# arca-2_0-box.net
KiCad netlist of a schematic drawn in EAGLE
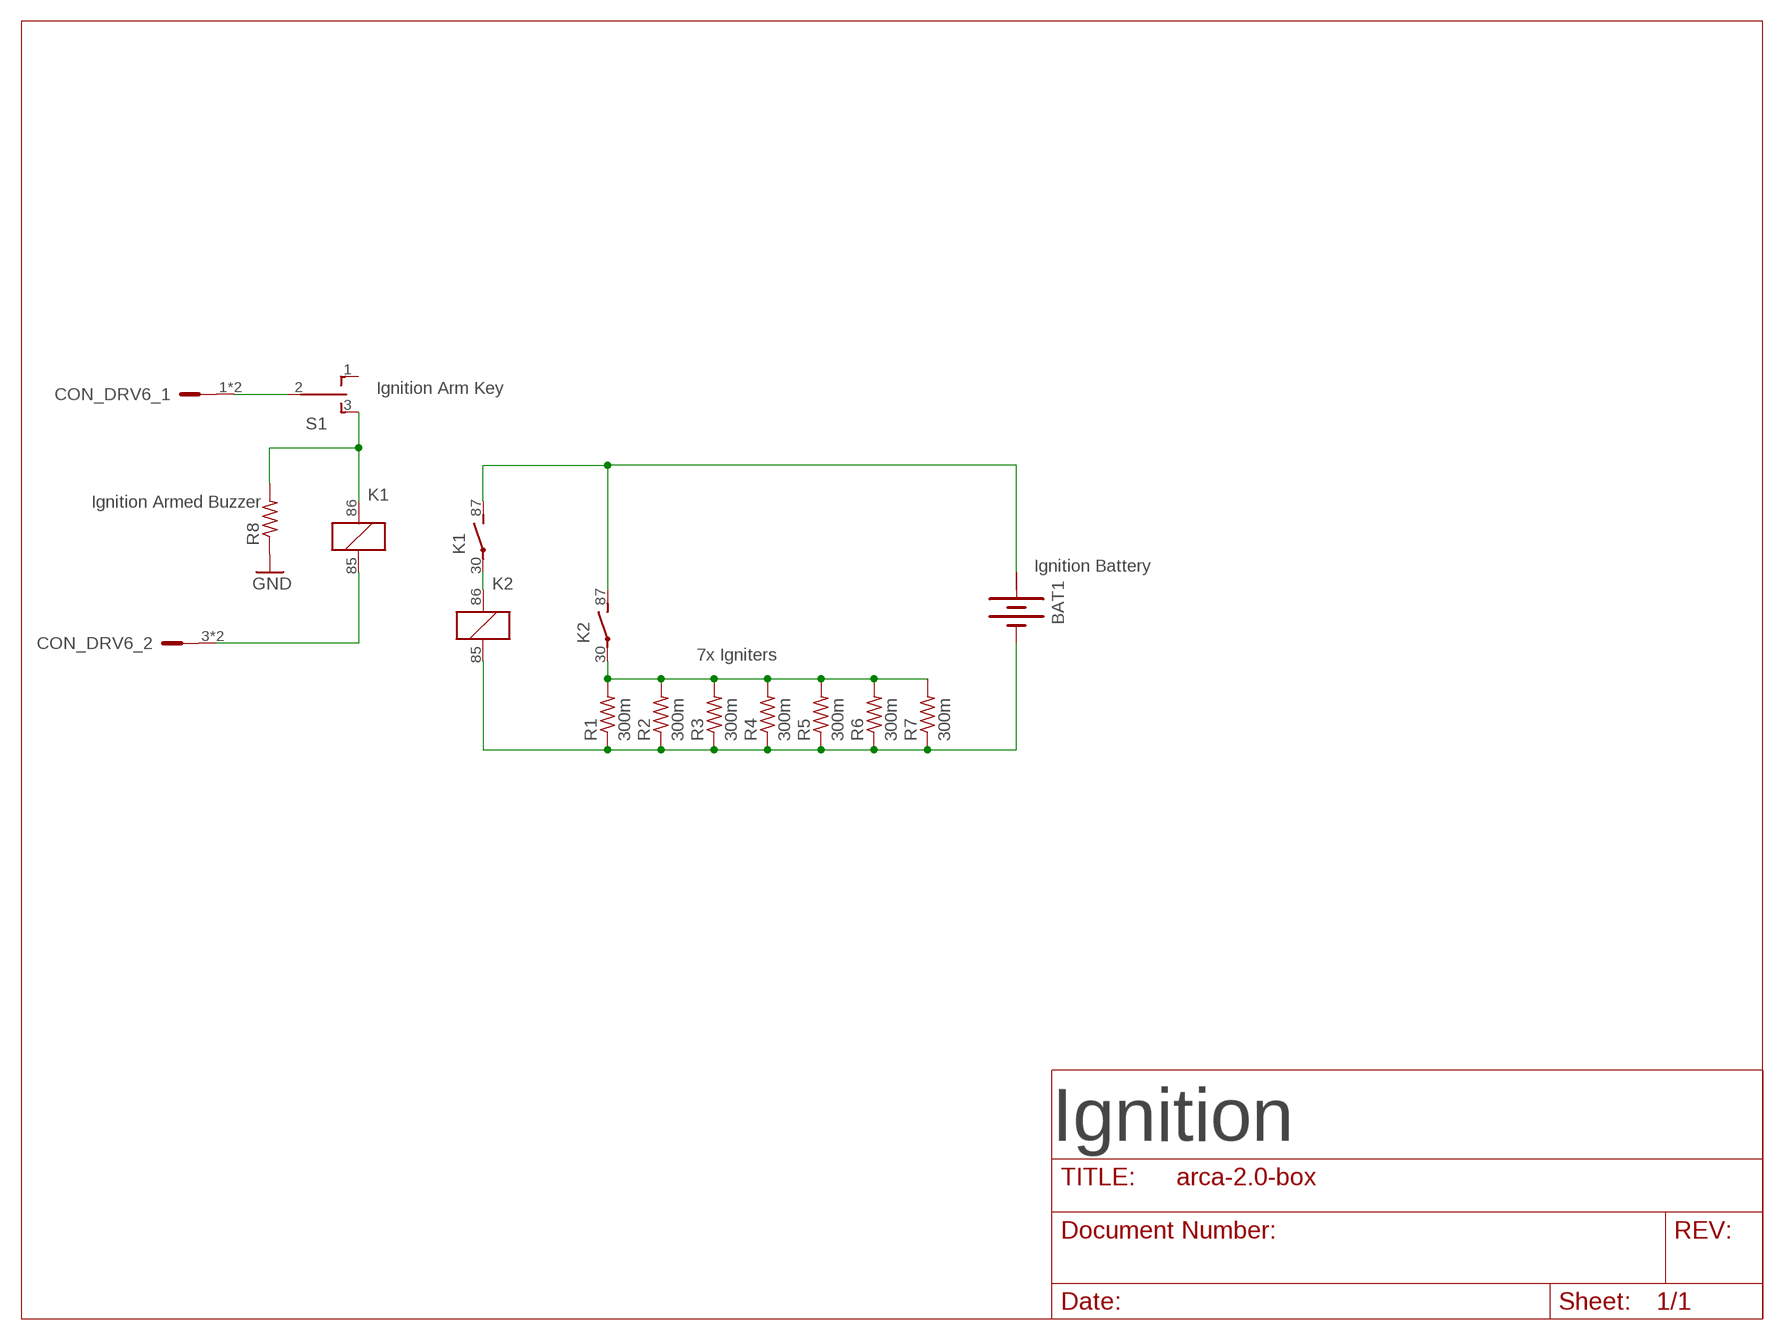
[diagram p0: schematic, sheet 1]

(export (version "E")
  (design (tool "Eeschema 10.0.6"))
  (components
    (comp (ref "BAT1")
      (value "BATTERY")
      (footprint "eagle-import:BATTERY")
      (libsource (lib "eagle-import") (part "BATTERY"))
    )
    (comp (ref "CON_DRV6")
      (value "LPTA-2POS")
      (footprint "eagle-import:8.2X2")
      (libsource (lib "eagle-import") (part "LPTA-2POS"))
    )
    (comp (ref "K1")
      (value "CB1A-P-12V")
      (footprint "eagle-import:CB1")
      (fields (field (name "MF") "AROMAT/ MATSUSHITA"))
      (libsource (lib "eagle-import") (part "CB1A-P-12V"))
    )
    (comp (ref "K2")
      (value "CB1A-P-12V")
      (footprint "eagle-import:CB1")
      (fields (field (name "MF") "AROMAT/ MATSUSHITA"))
      (libsource (lib "eagle-import") (part "CB1A-P-12V"))
    )
    (comp (ref "R1")
      (value "300m")
      (footprint "eagle-import:M0805")
      (libsource (lib "eagle-import") (part "R-US_M0805"))
    )
    (comp (ref "R2")
      (value "300m")
      (footprint "eagle-import:M0805")
      (libsource (lib "eagle-import") (part "R-US_M0805"))
    )
    (comp (ref "R3")
      (value "300m")
      (footprint "eagle-import:M0805")
      (libsource (lib "eagle-import") (part "R-US_M0805"))
    )
    (comp (ref "R4")
      (value "300m")
      (footprint "eagle-import:M0805")
      (libsource (lib "eagle-import") (part "R-US_M0805"))
    )
    (comp (ref "R5")
      (value "300m")
      (footprint "eagle-import:M0805")
      (libsource (lib "eagle-import") (part "R-US_M0805"))
    )
    (comp (ref "R6")
      (value "300m")
      (footprint "eagle-import:M0805")
      (libsource (lib "eagle-import") (part "R-US_M0805"))
    )
    (comp (ref "R7")
      (value "300m")
      (footprint "eagle-import:M0805")
      (libsource (lib "eagle-import") (part "R-US_M0805"))
    )
    (comp (ref "R8")
      (value "Ignition Armed Buzzer")
      (footprint "eagle-import:M0805")
      (libsource (lib "eagle-import") (part "R-US_M0805"))
    )
    (comp (ref "S1")
      (value "TL39PO")
      (footprint "eagle-import:TL3XPO")
      (libsource (lib "eagle-import") (part "TL39PO"))
    )
  )
  (nets
    (net (code "1") (name "/+") (class "Default")
      (node (ref "BAT1") (pin "+@1") (pinfunction "+_+@1") (pintype "power_in"))
    )
    (net (code "2") (name "GND") (class "Default")
      (node (ref "R8") (pin "1") (pinfunction "1_1") (pintype "passive"))
    )
    (net (code "3") (name "Net-(K1A-1)") (class "Default")
      (node (ref "K1") (pin "86") (pinfunction "1_86") (pintype "passive"))
      (node (ref "R8") (pin "2") (pinfunction "2_2") (pintype "passive"))
      (node (ref "S1") (pin "3") (pinfunction "S_3") (pintype "passive"))
    )
    (net (code "4") (name "Net-(K1A-2)") (class "Default")
      (node (ref "CON_DRV6") (pin "3") (pinfunction "SK_3") (pintype "passive"))
      (node (ref "CON_DRV6") (pin "4") (pinfunction "SK_4") (pintype "passive"))
      (node (ref "K1") (pin "85") (pinfunction "2_85") (pintype "passive"))
    )
    (net (code "5") (name "Net-(K1B-P)") (class "Default")
      (node (ref "K1") (pin "30") (pinfunction "P_30") (pintype "passive"))
      (node (ref "K2") (pin "86") (pinfunction "1_86") (pintype "passive"))
    )
    (net (code "6") (name "Net-(K1B-S)") (class "Default")
      (node (ref "BAT1") (pin "+") (pinfunction "+_+") (pintype "power_in"))
      (node (ref "K1") (pin "87") (pinfunction "S_87") (pintype "passive"))
      (node (ref "K2") (pin "87") (pinfunction "S_87") (pintype "passive"))
    )
    (net (code "7") (name "Net-(K2A-2)") (class "Default")
      (node (ref "BAT1") (pin "-") (pinfunction "-_-") (pintype "power_in"))
      (node (ref "K2") (pin "85") (pinfunction "2_85") (pintype "passive"))
      (node (ref "R1") (pin "1") (pinfunction "1_1") (pintype "passive"))
      (node (ref "R2") (pin "1") (pinfunction "1_1") (pintype "passive"))
      (node (ref "R3") (pin "1") (pinfunction "1_1") (pintype "passive"))
      (node (ref "R4") (pin "1") (pinfunction "1_1") (pintype "passive"))
      (node (ref "R5") (pin "1") (pinfunction "1_1") (pintype "passive"))
      (node (ref "R6") (pin "1") (pinfunction "1_1") (pintype "passive"))
      (node (ref "R7") (pin "1") (pinfunction "1_1") (pintype "passive"))
    )
    (net (code "8") (name "Net-(K2B-P)") (class "Default")
      (node (ref "K2") (pin "30") (pinfunction "P_30") (pintype "passive"))
      (node (ref "R1") (pin "2") (pinfunction "2_2") (pintype "passive"))
      (node (ref "R2") (pin "2") (pinfunction "2_2") (pintype "passive"))
      (node (ref "R3") (pin "2") (pinfunction "2_2") (pintype "passive"))
      (node (ref "R4") (pin "2") (pinfunction "2_2") (pintype "passive"))
      (node (ref "R5") (pin "2") (pinfunction "2_2") (pintype "passive"))
      (node (ref "R6") (pin "2") (pinfunction "2_2") (pintype "passive"))
      (node (ref "R7") (pin "2") (pinfunction "2_2") (pintype "passive"))
    )
    (net (code "9") (name "Net-(S1-P)") (class "Default")
      (node (ref "CON_DRV6") (pin "1") (pinfunction "SK_1") (pintype "passive"))
      (node (ref "CON_DRV6") (pin "2") (pinfunction "SK_2") (pintype "passive"))
      (node (ref "S1") (pin "2") (pinfunction "P_2") (pintype "passive"))
    )
    (net (code "10") (name "unconnected-(S1-O-Pad1)") (class "Default")
      (node (ref "S1") (pin "1") (pinfunction "O_1") (pintype "passive"))
    )
  )
)
